# Assam_police.net
KiCad netlist of a schematic drawn in EAGLE
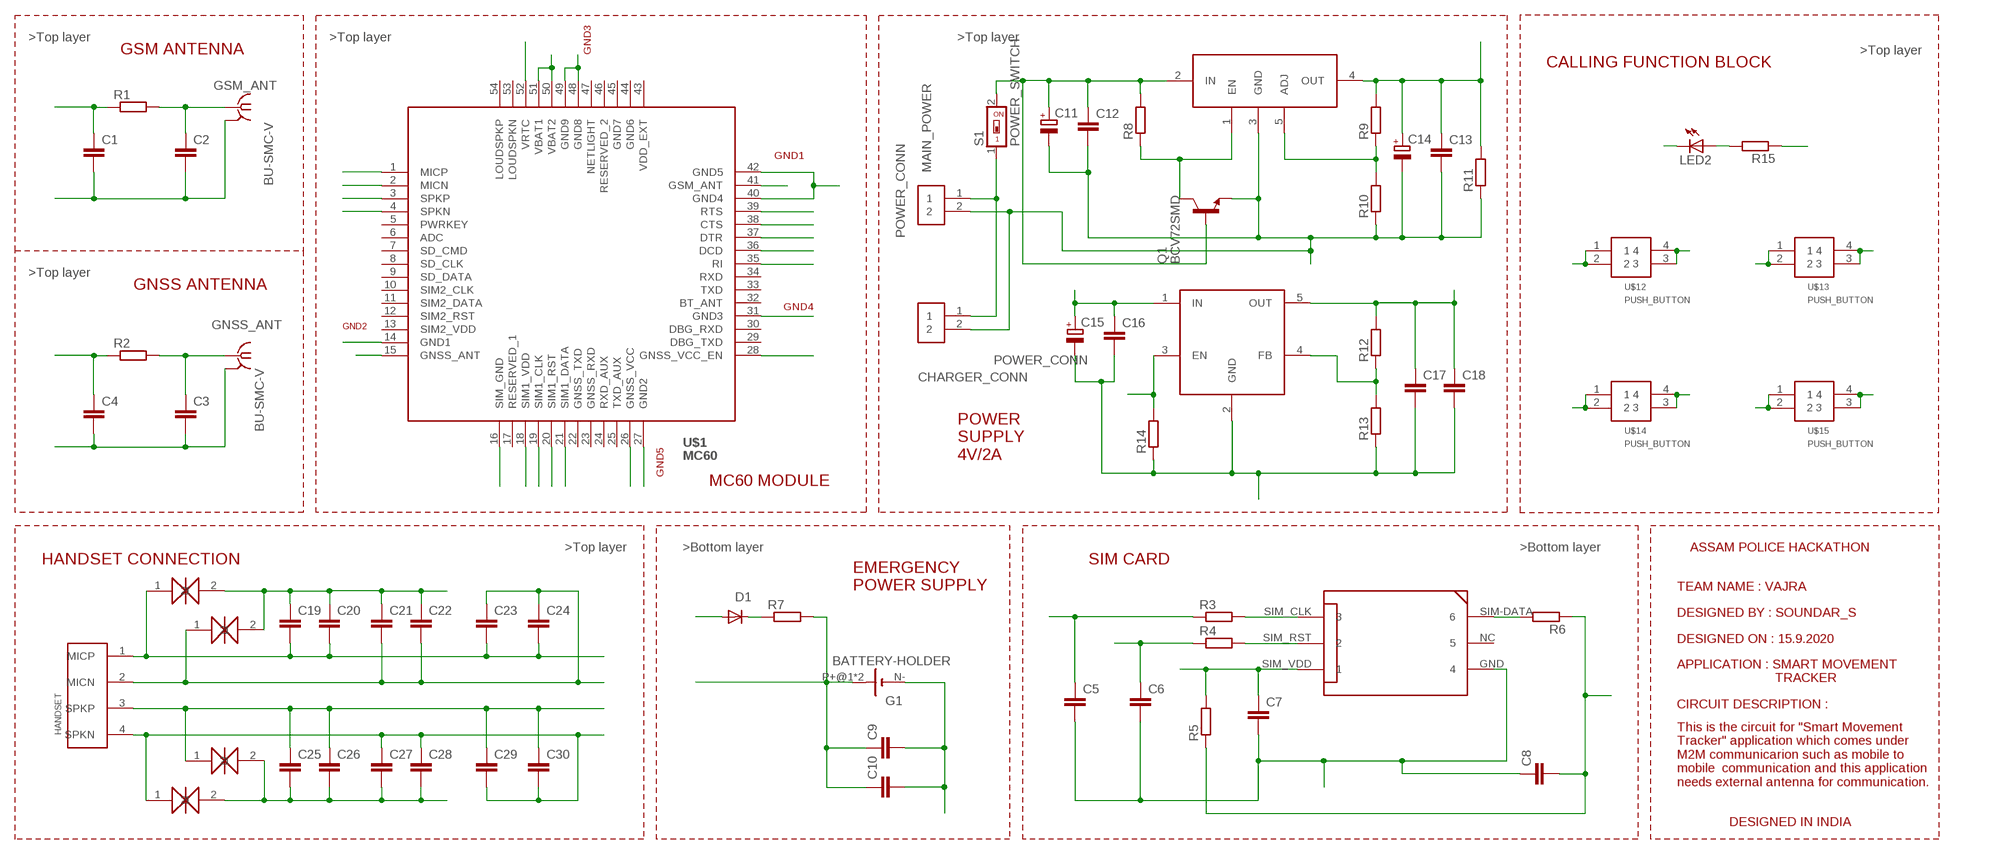
[diagram p0: schematic, sheet 1]

(export (version "E")
  (design (tool "Eeschema 10.0.6"))
  (components
    (comp (ref "C1")
      (value "C-EUC0603K")
      (footprint "eagle-import:C0603K")
      (libsource (lib "eagle-import") (part "C-EUC0603K"))
    )
    (comp (ref "C2")
      (value "C-EUC0603K")
      (footprint "eagle-import:C0603K")
      (libsource (lib "eagle-import") (part "C-EUC0603K"))
    )
    (comp (ref "C3")
      (value "C-EUC0603K")
      (footprint "eagle-import:C0603K")
      (libsource (lib "eagle-import") (part "C-EUC0603K"))
    )
    (comp (ref "C4")
      (value "C-EUC0603K")
      (footprint "eagle-import:C0603K")
      (libsource (lib "eagle-import") (part "C-EUC0603K"))
    )
    (comp (ref "C5")
      (value "C-EUC0603K")
      (footprint "eagle-import:C0603K")
      (libsource (lib "eagle-import") (part "C-EUC0603K"))
    )
    (comp (ref "C6")
      (value "C-EUC0603K")
      (footprint "eagle-import:C0603K")
      (libsource (lib "eagle-import") (part "C-EUC0603K"))
    )
    (comp (ref "C7")
      (value "C-EUC0603K")
      (footprint "eagle-import:C0603K")
      (libsource (lib "eagle-import") (part "C-EUC0603K"))
    )
    (comp (ref "C8")
      (value "C-EUC0603K")
      (footprint "eagle-import:C0603K")
      (libsource (lib "eagle-import") (part "C-EUC0603K"))
    )
    (comp (ref "C9")
      (value "C-EUC0603K")
      (footprint "eagle-import:C0603K")
      (libsource (lib "eagle-import") (part "C-EUC0603K"))
    )
    (comp (ref "C10")
      (value "C-EUC0603K")
      (footprint "eagle-import:C0603K")
      (libsource (lib "eagle-import") (part "C-EUC0603K"))
    )
    (comp (ref "C11")
      (value "CPOL-EU140CLH-0810")
      (footprint "eagle-import:140CLH-0810")
      (libsource (lib "eagle-import") (part "CPOL-EU140CLH-0810"))
    )
    (comp (ref "C12")
      (value "C-EUC1808")
      (footprint "eagle-import:C1808")
      (libsource (lib "eagle-import") (part "C-EUC1808"))
    )
    (comp (ref "C13")
      (value "C-EUC1808")
      (footprint "eagle-import:C1808")
      (libsource (lib "eagle-import") (part "C-EUC1808"))
    )
    (comp (ref "C14")
      (value "CPOL-EU140CLH-0810")
      (footprint "eagle-import:140CLH-0810")
      (libsource (lib "eagle-import") (part "CPOL-EU140CLH-0810"))
    )
    (comp (ref "C15")
      (value "CPOL-EU140CLH-0810")
      (footprint "eagle-import:140CLH-0810")
      (libsource (lib "eagle-import") (part "CPOL-EU140CLH-0810"))
    )
    (comp (ref "C16")
      (value "C-EUC1808")
      (footprint "eagle-import:C1808")
      (libsource (lib "eagle-import") (part "C-EUC1808"))
    )
    (comp (ref "C17")
      (value "C-EUC1808")
      (footprint "eagle-import:C1808")
      (libsource (lib "eagle-import") (part "C-EUC1808"))
    )
    (comp (ref "C18")
      (value "C-EUC1808")
      (footprint "eagle-import:C1808")
      (libsource (lib "eagle-import") (part "C-EUC1808"))
    )
    (comp (ref "C19")
      (value "C-EUC0603K")
      (footprint "eagle-import:C0603K")
      (libsource (lib "eagle-import") (part "C-EUC0603K"))
    )
    (comp (ref "C20")
      (value "C-EUC0603K")
      (footprint "eagle-import:C0603K")
      (libsource (lib "eagle-import") (part "C-EUC0603K"))
    )
    (comp (ref "C21")
      (value "C-EUC0603K")
      (footprint "eagle-import:C0603K")
      (libsource (lib "eagle-import") (part "C-EUC0603K"))
    )
    (comp (ref "C22")
      (value "C-EUC0603K")
      (footprint "eagle-import:C0603K")
      (libsource (lib "eagle-import") (part "C-EUC0603K"))
    )
    (comp (ref "C23")
      (value "C-EUC0603K")
      (footprint "eagle-import:C0603K")
      (libsource (lib "eagle-import") (part "C-EUC0603K"))
    )
    (comp (ref "C24")
      (value "C-EUC0603K")
      (footprint "eagle-import:C0603K")
      (libsource (lib "eagle-import") (part "C-EUC0603K"))
    )
    (comp (ref "C25")
      (value "C-EUC0603K")
      (footprint "eagle-import:C0603K")
      (libsource (lib "eagle-import") (part "C-EUC0603K"))
    )
    (comp (ref "C26")
      (value "C-EUC0603K")
      (footprint "eagle-import:C0603K")
      (libsource (lib "eagle-import") (part "C-EUC0603K"))
    )
    (comp (ref "C27")
      (value "C-EUC0603K")
      (footprint "eagle-import:C0603K")
      (libsource (lib "eagle-import") (part "C-EUC0603K"))
    )
    (comp (ref "C28")
      (value "C-EUC0603K")
      (footprint "eagle-import:C0603K")
      (libsource (lib "eagle-import") (part "C-EUC0603K"))
    )
    (comp (ref "C29")
      (value "C-EUC0603K")
      (footprint "eagle-import:C0603K")
      (libsource (lib "eagle-import") (part "C-EUC0603K"))
    )
    (comp (ref "C30")
      (value "C-EUC0603K")
      (footprint "eagle-import:C0603K")
      (libsource (lib "eagle-import") (part "C-EUC0603K"))
    )
    (comp (ref "CHARGER_CONN")
      (value "POWER_CONN")
      (footprint "eagle-import:POWER_PUSH_TYPE")
      (libsource (lib "eagle-import") (part "POWER_PUSH_TYPE_CONN"))
    )
    (comp (ref "D1")
      (value "CGRM4001-G")
      (footprint "eagle-import:SOD-123_MINI-SMA")
      (libsource (lib "eagle-import") (part "CGRM400-G1"))
    )
    (comp (ref "G1")
      (value "BATTERY-HOLDER")
      (footprint "eagle-import:CELL_RETAINER_11.6MM")
      (fields (field (name "MF") "KEYSTONE") (field (name "MPN") "2997"))
      (libsource (lib "eagle-import") (part "BATTERY-HOLDER_11.6MM"))
    )
    (comp (ref "GNSS_ANT")
      (value "BU-SMC-V")
      (footprint "eagle-import:BU-SMC-V")
      (libsource (lib "eagle-import") (part "BU-SMC-V"))
    )
    (comp (ref "GSM_ANT")
      (value "BU-SMC-V")
      (footprint "eagle-import:BU-SMC-V")
      (libsource (lib "eagle-import") (part "BU-SMC-V"))
    )
    (comp (ref "LED2")
      (value "LEDSMT1206")
      (footprint "eagle-import:1206")
      (libsource (lib "eagle-import") (part "LEDSMT1206"))
    )
    (comp (ref "MAIN_POWER")
      (value "POWER_CONN")
      (footprint "eagle-import:POWER_PUSH_TYPE")
      (libsource (lib "eagle-import") (part "POWER_PUSH_TYPE_CONN"))
    )
    (comp (ref "Q1")
      (value "BCV72SMD")
      (footprint "eagle-import:SOT23-BEC")
      (libsource (lib "eagle-import") (part "BCV72SMD"))
    )
    (comp (ref "R1")
      (value "R-EU_M3516")
      (footprint "eagle-import:M3516")
      (libsource (lib "eagle-import") (part "R-EU_M3516"))
    )
    (comp (ref "R2")
      (value "R-EU_M3516")
      (footprint "eagle-import:M3516")
      (libsource (lib "eagle-import") (part "R-EU_M3516"))
    )
    (comp (ref "R3")
      (value "R-EU_M3516")
      (footprint "eagle-import:M3516")
      (libsource (lib "eagle-import") (part "R-EU_M3516"))
    )
    (comp (ref "R4")
      (value "R-EU_M3516")
      (footprint "eagle-import:M3516")
      (libsource (lib "eagle-import") (part "R-EU_M3516"))
    )
    (comp (ref "R5")
      (value "R-EU_M3516")
      (footprint "eagle-import:M3516")
      (libsource (lib "eagle-import") (part "R-EU_M3516"))
    )
    (comp (ref "R6")
      (value "R-EU_M3516")
      (footprint "eagle-import:M3516")
      (libsource (lib "eagle-import") (part "R-EU_M3516"))
    )
    (comp (ref "R7")
      (value "R-EU_M3516")
      (footprint "eagle-import:M3516")
      (libsource (lib "eagle-import") (part "R-EU_M3516"))
    )
    (comp (ref "R8")
      (value "R-EU_MELF0207W")
      (footprint "eagle-import:MINI_MELF-0207W")
      (libsource (lib "eagle-import") (part "R-EU_MELF0207W"))
    )
    (comp (ref "R9")
      (value "R-EU_MELF0207W")
      (footprint "eagle-import:MINI_MELF-0207W")
      (libsource (lib "eagle-import") (part "R-EU_MELF0207W"))
    )
    (comp (ref "R10")
      (value "R-EU_MELF0207W")
      (footprint "eagle-import:MINI_MELF-0207W")
      (libsource (lib "eagle-import") (part "R-EU_MELF0207W"))
    )
    (comp (ref "R11")
      (value "R-EU_MELF0207W")
      (footprint "eagle-import:MINI_MELF-0207W")
      (libsource (lib "eagle-import") (part "R-EU_MELF0207W"))
    )
    (comp (ref "R12")
      (value "R-EU_MELF0207W")
      (footprint "eagle-import:MINI_MELF-0207W")
      (libsource (lib "eagle-import") (part "R-EU_MELF0207W"))
    )
    (comp (ref "R13")
      (value "R-EU_MELF0207W")
      (footprint "eagle-import:MINI_MELF-0207W")
      (libsource (lib "eagle-import") (part "R-EU_MELF0207W"))
    )
    (comp (ref "R14")
      (value "R-EU_MELF0207W")
      (footprint "eagle-import:MINI_MELF-0207W")
      (libsource (lib "eagle-import") (part "R-EU_MELF0207W"))
    )
    (comp (ref "R15")
      (value "R-EU_M3516")
      (footprint "eagle-import:M3516")
      (libsource (lib "eagle-import") (part "R-EU_M3516"))
    )
    (comp (ref "S1")
      (value "POWER_SWITCH")
      (footprint "eagle-import:SMS-001")
      (libsource (lib "eagle-import") (part "SWS001"))
    )
    (comp (ref "U$1")
      (value "MC60")
      (footprint "eagle-import:MC60")
      (libsource (lib "eagle-import") (part "MC60"))
    )
    (comp (ref "U$2")
      (value "SIM_MODULE")
      (footprint "eagle-import:SIM_6_SMD")
      (libsource (lib "eagle-import") (part "SIM_6_SMD"))
    )
    (comp (ref "U$3")
      (value "MIC29302")
      (footprint "eagle-import:TO-252")
      (libsource (lib "eagle-import") (part "MIC29302"))
    )
    (comp (ref "U$4")
      (value "SGM2019")
      (footprint "eagle-import:SGM2019")
      (libsource (lib "eagle-import") (part "SGM2019"))
    )
    (comp (ref "U$5")
      (value "HANDSET")
      (footprint "eagle-import:HANDSET_4")
      (libsource (lib "eagle-import") (part "HANDSET_4_PIN"))
    )
    (comp (ref "U$6")
      (value "ESD_DIODE")
      (footprint "eagle-import:ESD_PROTECTION_DIODE")
      (libsource (lib "eagle-import") (part "ESD_PRO_DIODE_1"))
    )
    (comp (ref "U$7")
      (value "ESD_DIODE")
      (footprint "eagle-import:ESD_PROTECTION_DIODE")
      (libsource (lib "eagle-import") (part "ESD_PRO_DIODE_1"))
    )
    (comp (ref "U$8")
      (value "ESD_DIODE")
      (footprint "eagle-import:ESD_PROTECTION_DIODE")
      (libsource (lib "eagle-import") (part "ESD_PRO_DIODE_1"))
    )
    (comp (ref "U$9")
      (value "ESD_DIODE")
      (footprint "eagle-import:ESD_PROTECTION_DIODE")
      (libsource (lib "eagle-import") (part "ESD_PRO_DIODE_1"))
    )
    (comp (ref "U$12")
      (value "PUSH_BUTTON")
      (footprint "eagle-import:PUSH_BUTTON")
      (libsource (lib "eagle-import") (part "PUSH_BUTTON_4"))
    )
    (comp (ref "U$13")
      (value "PUSH_BUTTON")
      (footprint "eagle-import:PUSH_BUTTON")
      (libsource (lib "eagle-import") (part "PUSH_BUTTON_4"))
    )
    (comp (ref "U$14")
      (value "PUSH_BUTTON")
      (footprint "eagle-import:PUSH_BUTTON")
      (libsource (lib "eagle-import") (part "PUSH_BUTTON_4"))
    )
    (comp (ref "U$15")
      (value "PUSH_BUTTON")
      (footprint "eagle-import:PUSH_BUTTON")
      (libsource (lib "eagle-import") (part "PUSH_BUTTON_4"))
    )
  )
  (nets
    (net (code "1") (name "/CALL_CUT0") (class "Default")
      (node (ref "U$1") (pin "37") (pinfunction "DTR_37") (pintype "bidirectional"))
      (node (ref "U$13") (pin "1") (pinfunction "1_1") (pintype "bidirectional"))
      (node (ref "U$13") (pin "2") (pinfunction "2_2") (pintype "bidirectional"))
    )
    (net (code "2") (name "/CALL_CUT1") (class "Default")
      (node (ref "U$1") (pin "35") (pinfunction "RI_35") (pintype "bidirectional"))
      (node (ref "U$15") (pin "1") (pinfunction "1_1") (pintype "bidirectional"))
      (node (ref "U$15") (pin "2") (pinfunction "2_2") (pintype "bidirectional"))
    )
    (net (code "3") (name "/CALL_MAKING") (class "Default")
      (node (ref "U$1") (pin "36") (pinfunction "DCD_36") (pintype "bidirectional"))
      (node (ref "U$14") (pin "1") (pinfunction "1_1") (pintype "bidirectional"))
      (node (ref "U$14") (pin "2") (pinfunction "2_2") (pintype "bidirectional"))
    )
    (net (code "4") (name "/CALL_PICKING") (class "Default")
      (node (ref "U$1") (pin "38") (pinfunction "CTS_38") (pintype "bidirectional"))
      (node (ref "U$12") (pin "1") (pinfunction "1_1") (pintype "bidirectional"))
      (node (ref "U$12") (pin "2") (pinfunction "2_2") (pintype "bidirectional"))
    )
    (net (code "5") (name "/GND1") (class "Default")
      (node (ref "C1") (pin "2") (pinfunction "2_2") (pintype "passive"))
      (node (ref "C2") (pin "2") (pinfunction "2_2") (pintype "passive"))
      (node (ref "GSM_ANT") (pin "2") (pinfunction "2_2") (pintype "passive"))
      (node (ref "GSM_ANT") (pin "3") (pinfunction "2_3") (pintype "passive"))
      (node (ref "GSM_ANT") (pin "4") (pinfunction "2_4") (pintype "passive"))
      (node (ref "GSM_ANT") (pin "5") (pinfunction "2_5") (pintype "passive"))
      (node (ref "LED2") (pin "C") (pinfunction "C_C") (pintype "passive"))
      (node (ref "U$1") (pin "40") (pinfunction "GND4_40") (pintype "bidirectional"))
      (node (ref "U$1") (pin "42") (pinfunction "GND5_42") (pintype "bidirectional"))
    )
    (net (code "6") (name "/GND2") (class "Default")
      (node (ref "C19") (pin "1") (pinfunction "1_1") (pintype "passive"))
      (node (ref "C20") (pin "1") (pinfunction "1_1") (pintype "passive"))
      (node (ref "C21") (pin "1") (pinfunction "1_1") (pintype "passive"))
      (node (ref "C22") (pin "1") (pinfunction "1_1") (pintype "passive"))
      (node (ref "C25") (pin "2") (pinfunction "2_2") (pintype "passive"))
      (node (ref "C26") (pin "2") (pinfunction "2_2") (pintype "passive"))
      (node (ref "C27") (pin "2") (pinfunction "2_2") (pintype "passive"))
      (node (ref "C28") (pin "2") (pinfunction "2_2") (pintype "passive"))
      (node (ref "C3") (pin "2") (pinfunction "2_2") (pintype "passive"))
      (node (ref "C4") (pin "2") (pinfunction "2_2") (pintype "passive"))
      (node (ref "GNSS_ANT") (pin "2") (pinfunction "2_2") (pintype "passive"))
      (node (ref "GNSS_ANT") (pin "3") (pinfunction "2_3") (pintype "passive"))
      (node (ref "GNSS_ANT") (pin "4") (pinfunction "2_4") (pintype "passive"))
      (node (ref "GNSS_ANT") (pin "5") (pinfunction "2_5") (pintype "passive"))
      (node (ref "U$1") (pin "14") (pinfunction "GND1_14") (pintype "bidirectional"))
      (node (ref "U$6") (pin "2") (pinfunction "2_2") (pintype "bidirectional"))
      (node (ref "U$7") (pin "2") (pinfunction "2_2") (pintype "bidirectional"))
      (node (ref "U$8") (pin "2") (pinfunction "2_2") (pintype "bidirectional"))
      (node (ref "U$9") (pin "2") (pinfunction "2_2") (pintype "bidirectional"))
    )
    (net (code "7") (name "/GND3") (class "Default")
      (node (ref "C10") (pin "2") (pinfunction "2_2") (pintype "passive"))
      (node (ref "C11") (pin "-") (pinfunction "-_-") (pintype "passive"))
      (node (ref "C12") (pin "2") (pinfunction "2_2") (pintype "passive"))
      (node (ref "C13") (pin "2") (pinfunction "2_2") (pintype "passive"))
      (node (ref "C14") (pin "-") (pinfunction "-_-") (pintype "passive"))
      (node (ref "C9") (pin "2") (pinfunction "2_2") (pintype "passive"))
      (node (ref "CHARGER_CONN") (pin "2") (pinfunction "2_2") (pintype "bidirectional"))
      (node (ref "G1") (pin "N-") (pinfunction "-_N-") (pintype "passive"))
      (node (ref "MAIN_POWER") (pin "2") (pinfunction "2_2") (pintype "bidirectional"))
      (node (ref "Q1") (pin "E") (pinfunction "E_E") (pintype "passive"))
      (node (ref "R10") (pin "1") (pinfunction "1_1") (pintype "passive"))
      (node (ref "R11") (pin "1") (pinfunction "1_1") (pintype "passive"))
      (node (ref "U$1") (pin "48") (pinfunction "GND8_48") (pintype "bidirectional"))
      (node (ref "U$1") (pin "49") (pinfunction "GND9_49") (pintype "bidirectional"))
      (node (ref "U$3") (pin "3") (pinfunction "GND_3") (pintype "bidirectional"))
    )
    (net (code "8") (name "/GND5") (class "Default")
      (node (ref "C15") (pin "-") (pinfunction "-_-") (pintype "passive"))
      (node (ref "C16") (pin "2") (pinfunction "2_2") (pintype "passive"))
      (node (ref "C17") (pin "2") (pinfunction "2_2") (pintype "passive"))
      (node (ref "C18") (pin "2") (pinfunction "2_2") (pintype "passive"))
      (node (ref "R13") (pin "1") (pinfunction "1_1") (pintype "passive"))
      (node (ref "R14") (pin "1") (pinfunction "1_1") (pintype "passive"))
      (node (ref "U$1") (pin "27") (pinfunction "GND2_27") (pintype "bidirectional"))
      (node (ref "U$4") (pin "2") (pinfunction "GND_2") (pintype "bidirectional"))
    )
    (net (code "9") (name "/GNSS_ANT") (class "Default")
      (node (ref "C4") (pin "1") (pinfunction "1_1") (pintype "passive"))
      (node (ref "R2") (pin "1") (pinfunction "1_1") (pintype "passive"))
      (node (ref "U$1") (pin "15") (pinfunction "GNSS_ANT_15") (pintype "bidirectional"))
    )
    (net (code "10") (name "/GNSS_VCC") (class "Default")
      (node (ref "C17") (pin "1") (pinfunction "1_1") (pintype "passive"))
      (node (ref "C18") (pin "1") (pinfunction "1_1") (pintype "passive"))
      (node (ref "R12") (pin "2") (pinfunction "2_2") (pintype "passive"))
      (node (ref "U$1") (pin "26") (pinfunction "GNSS_VCC_26") (pintype "bidirectional"))
      (node (ref "U$4") (pin "5") (pinfunction "OUT_5") (pintype "bidirectional"))
    )
    (net (code "11") (name "/GNSS_VCC_EN") (class "Default")
      (node (ref "R14") (pin "2") (pinfunction "2_2") (pintype "passive"))
      (node (ref "U$1") (pin "28") (pinfunction "GNSS_VCC_EN_28") (pintype "bidirectional"))
      (node (ref "U$4") (pin "3") (pinfunction "EN_3") (pintype "bidirectional"))
    )
    (net (code "12") (name "/GSM_ANT") (class "Default")
      (node (ref "C1") (pin "1") (pinfunction "1_1") (pintype "passive"))
      (node (ref "R1") (pin "1") (pinfunction "1_1") (pintype "passive"))
      (node (ref "U$1") (pin "41") (pinfunction "GSM_ANT_41") (pintype "bidirectional"))
    )
    (net (code "13") (name "/INCOMMING_CALL_INDI") (class "Default")
      (node (ref "R15") (pin "1") (pinfunction "1_1") (pintype "passive"))
      (node (ref "U$1") (pin "39") (pinfunction "RTS_39") (pintype "bidirectional"))
    )
    (net (code "14") (name "/MICN") (class "Default")
      (node (ref "C21") (pin "2") (pinfunction "2_2") (pintype "passive"))
      (node (ref "C22") (pin "2") (pinfunction "2_2") (pintype "passive"))
      (node (ref "C23") (pin "1") (pinfunction "1_1") (pintype "passive"))
      (node (ref "C24") (pin "1") (pinfunction "1_1") (pintype "passive"))
      (node (ref "U$1") (pin "2") (pinfunction "MICN_2") (pintype "bidirectional"))
      (node (ref "U$5") (pin "2") (pinfunction "MICN_2") (pintype "bidirectional"))
      (node (ref "U$7") (pin "1") (pinfunction "1_1") (pintype "bidirectional"))
    )
    (net (code "15") (name "/MICP") (class "Default")
      (node (ref "C19") (pin "2") (pinfunction "2_2") (pintype "passive"))
      (node (ref "C20") (pin "2") (pinfunction "2_2") (pintype "passive"))
      (node (ref "C23") (pin "2") (pinfunction "2_2") (pintype "passive"))
      (node (ref "C24") (pin "2") (pinfunction "2_2") (pintype "passive"))
      (node (ref "U$1") (pin "1") (pinfunction "MICP_1") (pintype "bidirectional"))
      (node (ref "U$5") (pin "1") (pinfunction "MICP_1") (pintype "bidirectional"))
      (node (ref "U$6") (pin "1") (pinfunction "1_1") (pintype "bidirectional"))
    )
    (net (code "16") (name "/SIM_CLK") (class "Default")
      (node (ref "C5") (pin "1") (pinfunction "1_1") (pintype "passive"))
      (node (ref "R3") (pin "1") (pinfunction "1_1") (pintype "passive"))
      (node (ref "U$1") (pin "19") (pinfunction "SIM1_CLK_19") (pintype "bidirectional"))
    )
    (net (code "17") (name "/SIM_DATA") (class "Default")
      (node (ref "C8") (pin "2") (pinfunction "2_2") (pintype "passive"))
      (node (ref "R5") (pin "1") (pinfunction "1_1") (pintype "passive"))
      (node (ref "R6") (pin "1") (pinfunction "1_1") (pintype "passive"))
      (node (ref "U$1") (pin "21") (pinfunction "SIM1_DATA_21") (pintype "bidirectional"))
    )
    (net (code "18") (name "/SIM_GND") (class "Default")
      (node (ref "C5") (pin "2") (pinfunction "2_2") (pintype "passive"))
      (node (ref "C6") (pin "2") (pinfunction "2_2") (pintype "passive"))
      (node (ref "C7") (pin "2") (pinfunction "2_2") (pintype "passive"))
      (node (ref "C8") (pin "1") (pinfunction "1_1") (pintype "passive"))
      (node (ref "U$1") (pin "16") (pinfunction "SIM_GND_16") (pintype "bidirectional"))
      (node (ref "U$2") (pin "GND") (pinfunction "4_GND") (pintype "bidirectional"))
    )
    (net (code "19") (name "/SIM_RST") (class "Default")
      (node (ref "C6") (pin "1") (pinfunction "1_1") (pintype "passive"))
      (node (ref "R4") (pin "1") (pinfunction "1_1") (pintype "passive"))
      (node (ref "U$1") (pin "20") (pinfunction "SIM1_RST_20") (pintype "bidirectional"))
    )
    (net (code "20") (name "/SIM_VDD") (class "Default")
      (node (ref "C7") (pin "1") (pinfunction "1_1") (pintype "passive"))
      (node (ref "R5") (pin "2") (pinfunction "2_2") (pintype "passive"))
      (node (ref "U$1") (pin "18") (pinfunction "SIM1_VDD_18") (pintype "bidirectional"))
      (node (ref "U$2") (pin "SIM_VDD") (pinfunction "1_SIM_VDD") (pintype "bidirectional"))
    )
    (net (code "21") (name "/SPKN") (class "Default")
      (node (ref "C27") (pin "1") (pinfunction "1_1") (pintype "passive"))
      (node (ref "C28") (pin "1") (pinfunction "1_1") (pintype "passive"))
      (node (ref "C29") (pin "2") (pinfunction "2_2") (pintype "passive"))
      (node (ref "C30") (pin "2") (pinfunction "2_2") (pintype "passive"))
      (node (ref "U$1") (pin "4") (pinfunction "SPKN_4") (pintype "bidirectional"))
      (node (ref "U$5") (pin "4") (pinfunction "SPKN_4") (pintype "bidirectional"))
      (node (ref "U$9") (pin "1") (pinfunction "1_1") (pintype "bidirectional"))
    )
    (net (code "22") (name "/SPKP") (class "Default")
      (node (ref "C25") (pin "1") (pinfunction "1_1") (pintype "passive"))
      (node (ref "C26") (pin "1") (pinfunction "1_1") (pintype "passive"))
      (node (ref "C29") (pin "1") (pinfunction "1_1") (pintype "passive"))
      (node (ref "C30") (pin "1") (pinfunction "1_1") (pintype "passive"))
      (node (ref "U$1") (pin "3") (pinfunction "SPKP_3") (pintype "bidirectional"))
      (node (ref "U$5") (pin "3") (pinfunction "SPKP_3") (pintype "bidirectional"))
      (node (ref "U$8") (pin "1") (pinfunction "1_1") (pintype "bidirectional"))
    )
    (net (code "23") (name "/VBAT") (class "Default")
      (node (ref "C13") (pin "1") (pinfunction "1_1") (pintype "passive"))
      (node (ref "C14") (pin "+") (pinfunction "+_+") (pintype "passive"))
      (node (ref "C15") (pin "+") (pinfunction "+_+") (pintype "passive"))
      (node (ref "C16") (pin "1") (pinfunction "1_1") (pintype "passive"))
      (node (ref "D1") (pin "A") (pinfunction "A_A") (pintype "passive"))
      (node (ref "R11") (pin "2") (pinfunction "2_2") (pintype "passive"))
      (node (ref "R9") (pin "2") (pinfunction "2_2") (pintype "passive"))
      (node (ref "U$1") (pin "50") (pinfunction "VBAT2_50") (pintype "bidirectional"))
      (node (ref "U$1") (pin "51") (pinfunction "VBAT1_51") (pintype "bidirectional"))
      (node (ref "U$12") (pin "3") (pinfunction "3_3") (pintype "bidirectional"))
      (node (ref "U$12") (pin "4") (pinfunction "4_4") (pintype "bidirectional"))
      (node (ref "U$13") (pin "3") (pinfunction "3_3") (pintype "bidirectional"))
      (node (ref "U$13") (pin "4") (pinfunction "4_4") (pintype "bidirectional"))
      (node (ref "U$14") (pin "3") (pinfunction "3_3") (pintype "bidirectional"))
      (node (ref "U$14") (pin "4") (pinfunction "4_4") (pintype "bidirectional"))
      (node (ref "U$15") (pin "3") (pinfunction "3_3") (pintype "bidirectional"))
      (node (ref "U$15") (pin "4") (pinfunction "4_4") (pintype "bidirectional"))
      (node (ref "U$3") (pin "4") (pinfunction "OUT_4") (pintype "bidirectional"))
      (node (ref "U$4") (pin "1") (pinfunction "IN_1") (pintype "bidirectional"))
    )
    (net (code "24") (name "/VRTC") (class "Default")
      (node (ref "C10") (pin "1") (pinfunction "1_1") (pintype "passive"))
      (node (ref "C9") (pin "1") (pinfunction "1_1") (pintype "passive"))
      (node (ref "G1") (pin "P+@1") (pinfunction "+_P+@1") (pintype "passive"))
      (node (ref "G1") (pin "P+@2") (pinfunction "+_P+@2") (pintype "passive"))
      (node (ref "R7") (pin "2") (pinfunction "2_2") (pintype "passive"))
      (node (ref "U$1") (pin "52") (pinfunction "VRTC_52") (pintype "bidirectional"))
    )
    (net (code "25") (name "Net-(C2-Pad1)") (class "Default")
      (node (ref "C2") (pin "1") (pinfunction "1_1") (pintype "passive"))
      (node (ref "GSM_ANT") (pin "1") (pinfunction "1_1") (pintype "passive"))
      (node (ref "R1") (pin "2") (pinfunction "2_2") (pintype "passive"))
    )
    (net (code "26") (name "Net-(C3-Pad1)") (class "Default")
      (node (ref "C3") (pin "1") (pinfunction "1_1") (pintype "passive"))
      (node (ref "GNSS_ANT") (pin "1") (pinfunction "1_1") (pintype "passive"))
      (node (ref "R2") (pin "2") (pinfunction "2_2") (pintype "passive"))
    )
    (net (code "27") (name "Net-(CHARGER_CONN-Pad1)") (class "Default")
      (node (ref "CHARGER_CONN") (pin "1") (pinfunction "1_1") (pintype "bidirectional"))
      (node (ref "MAIN_POWER") (pin "1") (pinfunction "1_1") (pintype "bidirectional"))
      (node (ref "S1") (pin "1") (pinfunction "1_1") (pintype "passive"))
    )
    (net (code "28") (name "Net-(D1-PadC)") (class "Default")
      (node (ref "D1") (pin "C") (pinfunction "C_C") (pintype "passive"))
      (node (ref "R7") (pin "1") (pinfunction "1_1") (pintype "passive"))
    )
    (net (code "29") (name "Net-(LED2-PadA)") (class "Default")
      (node (ref "LED2") (pin "A") (pinfunction "A_A") (pintype "passive"))
      (node (ref "R15") (pin "2") (pinfunction "2_2") (pintype "passive"))
    )
    (net (code "30") (name "Net-(U$2-2)") (class "Default")
      (node (ref "R4") (pin "2") (pinfunction "2_2") (pintype "passive"))
      (node (ref "U$2") (pin "SIM_RST") (pinfunction "2_SIM_RST") (pintype "bidirectional"))
    )
    (net (code "31") (name "Net-(U$2-3)") (class "Default")
      (node (ref "R3") (pin "2") (pinfunction "2_2") (pintype "passive"))
      (node (ref "U$2") (pin "SIM_CLK") (pinfunction "3_SIM_CLK") (pintype "bidirectional"))
    )
    (net (code "32") (name "Net-(U$2-6)") (class "Default")
      (node (ref "R6") (pin "2") (pinfunction "2_2") (pintype "passive"))
      (node (ref "U$2") (pin "SIM-DATA") (pinfunction "6_SIM-DATA") (pintype "bidirectional"))
    )
    (net (code "33") (name "Net-(U$3-ADJ)") (class "Default")
      (node (ref "R10") (pin "2") (pinfunction "2_2") (pintype "passive"))
      (node (ref "R9") (pin "1") (pinfunction "1_1") (pintype "passive"))
      (node (ref "U$3") (pin "5") (pinfunction "ADJ_5") (pintype "bidirectional"))
    )
    (net (code "34") (name "Net-(U$3-EN)") (class "Default")
      (node (ref "Q1") (pin "C") (pinfunction "C_C") (pintype "passive"))
      (node (ref "R8") (pin "1") (pinfunction "1_1") (pintype "passive"))
      (node (ref "U$3") (pin "1") (pinfunction "EN_1") (pintype "bidirectional"))
    )
    (net (code "35") (name "Net-(U$3-IN)") (class "Default")
      (node (ref "C11") (pin "+") (pinfunction "+_+") (pintype "passive"))
      (node (ref "C12") (pin "1") (pinfunction "1_1") (pintype "passive"))
      (node (ref "Q1") (pin "B") (pinfunction "B_B") (pintype "passive"))
      (node (ref "R8") (pin "2") (pinfunction "2_2") (pintype "passive"))
      (node (ref "S1") (pin "2") (pinfunction "2_2") (pintype "passive"))
      (node (ref "U$3") (pin "2") (pinfunction "IN_2") (pintype "bidirectional"))
    )
    (net (code "36") (name "Net-(U$4-FB)") (class "Default")
      (node (ref "R12") (pin "1") (pinfunction "1_1") (pintype "passive"))
      (node (ref "R13") (pin "2") (pinfunction "2_2") (pintype "passive"))
      (node (ref "U$4") (pin "4") (pinfunction "FB_4") (pintype "bidirectional"))
    )
    (net (code "37") (name "unconnected-(U$1-ADC-Pad6)") (class "Default")
      (node (ref "U$1") (pin "6") (pinfunction "ADC_6") (pintype "bidirectional"))
    )
    (net (code "38") (name "unconnected-(U$1-BT_ANT-Pad32)") (class "Default")
      (node (ref "U$1") (pin "32") (pinfunction "BT_ANT_32") (pintype "bidirectional"))
    )
    (net (code "39") (name "unconnected-(U$1-DBG_RXD-Pad30)") (class "Default")
      (node (ref "U$1") (pin "30") (pinfunction "DBG_RXD_30") (pintype "bidirectional"))
    )
    (net (code "40") (name "unconnected-(U$1-DBG_TXD-Pad29)") (class "Default")
      (node (ref "U$1") (pin "29") (pinfunction "DBG_TXD_29") (pintype "bidirectional"))
    )
    (net (code "41") (name "unconnected-(U$1-GND3-Pad31)") (class "Default")
      (node (ref "U$1") (pin "31") (pinfunction "GND3_31") (pintype "bidirectional"))
    )
    (net (code "42") (name "unconnected-(U$1-GND6-Pad44)") (class "Default")
      (node (ref "U$1") (pin "44") (pinfunction "GND6_44") (pintype "bidirectional"))
    )
    (net (code "43") (name "unconnected-(U$1-GND7-Pad45)") (class "Default")
      (node (ref "U$1") (pin "45") (pinfunction "GND7_45") (pintype "bidirectional"))
    )
    (net (code "44") (name "unconnected-(U$1-GNSS_RXD-Pad23)") (class "Default")
      (node (ref "U$1") (pin "23") (pinfunction "GNSS_RXD_23") (pintype "bidirectional"))
    )
    (net (code "45") (name "unconnected-(U$1-GNSS_TXD-Pad22)") (class "Default")
      (node (ref "U$1") (pin "22") (pinfunction "GNSS_TXD_22") (pintype "bidirectional"))
    )
    (net (code "46") (name "unconnected-(U$1-LOUDSPKN-Pad53)") (class "Default")
      (node (ref "U$1") (pin "53") (pinfunction "LOUDSPKN_53") (pintype "bidirectional"))
    )
    (net (code "47") (name "unconnected-(U$1-LOUDSPKP-Pad54)") (class "Default")
      (node (ref "U$1") (pin "54") (pinfunction "LOUDSPKP_54") (pintype "bidirectional"))
    )
    (net (code "48") (name "unconnected-(U$1-NETLIGHT-Pad47)") (class "Default")
      (node (ref "U$1") (pin "47") (pinfunction "NETLIGHT_47") (pintype "bidirectional"))
    )
    (net (code "49") (name "unconnected-(U$1-PWRKEY-Pad5)") (class "Default")
      (node (ref "U$1") (pin "5") (pinfunction "PWRKEY_5") (pintype "bidirectional"))
    )
    (net (code "50") (name "unconnected-(U$1-RESERVED_1-Pad17)") (class "Default")
      (node (ref "U$1") (pin "17") (pinfunction "RESERVED_1_17") (pintype "bidirectional"))
    )
    (net (code "51") (name "unconnected-(U$1-RESERVED_2-Pad46)") (class "Default")
      (node (ref "U$1") (pin "46") (pinfunction "RESERVED_2_46") (pintype "bidirectional"))
    )
    (net (code "52") (name "unconnected-(U$1-RXD-Pad34)") (class "Default")
      (node (ref "U$1") (pin "34") (pinfunction "RXD_34") (pintype "bidirectional"))
    )
    (net (code "53") (name "unconnected-(U$1-RXD_AUX-Pad24)") (class "Default")
      (node (ref "U$1") (pin "24") (pinfunction "RXD_AUX_24") (pintype "bidirectional"))
    )
    (net (code "54") (name "unconnected-(U$1-SD_CLK-Pad8)") (class "Default")
      (node (ref "U$1") (pin "8") (pinfunction "SD_CLK_8") (pintype "bidirectional"))
    )
    (net (code "55") (name "unconnected-(U$1-SD_CMD-Pad7)") (class "Default")
      (node (ref "U$1") (pin "7") (pinfunction "SD_CMD_7") (pintype "bidirectional"))
    )
    (net (code "56") (name "unconnected-(U$1-SD_DATA-Pad9)") (class "Default")
      (node (ref "U$1") (pin "9") (pinfunction "SD_DATA_9") (pintype "bidirectional"))
    )
    (net (code "57") (name "unconnected-(U$1-SIM2_CLK-Pad10)") (class "Default")
      (node (ref "U$1") (pin "10") (pinfunction "SIM2_CLK_10") (pintype "bidirectional"))
    )
    (net (code "58") (name "unconnected-(U$1-SIM2_DATA-Pad11)") (class "Default")
      (node (ref "U$1") (pin "11") (pinfunction "SIM2_DATA_11") (pintype "bidirectional"))
    )
    (net (code "59") (name "unconnected-(U$1-SIM2_RST-Pad12)") (class "Default")
      (node (ref "U$1") (pin "12") (pinfunction "SIM2_RST_12") (pintype "bidirectional"))
    )
    (net (code "60") (name "unconnected-(U$1-SIM2_VDD-Pad13)") (class "Default")
      (node (ref "U$1") (pin "13") (pinfunction "SIM2_VDD_13") (pintype "bidirectional"))
    )
    (net (code "61") (name "unconnected-(U$1-TXD-Pad33)") (class "Default")
      (node (ref "U$1") (pin "33") (pinfunction "TXD_33") (pintype "bidirectional"))
    )
    (net (code "62") (name "unconnected-(U$1-TXD_AUX-Pad25)") (class "Default")
      (node (ref "U$1") (pin "25") (pinfunction "TXD_AUX_25") (pintype "bidirectional"))
    )
    (net (code "63") (name "unconnected-(U$1-VDD_EXT-Pad43)") (class "Default")
      (node (ref "U$1") (pin "43") (pinfunction "VDD_EXT_43") (pintype "bidirectional"))
    )
    (net (code "64") (name "unconnected-(U$2-5-PadNC)") (class "Default")
      (node (ref "U$2") (pin "NC") (pinfunction "5_NC") (pintype "bidirectional"))
    )
  )
)
